# ESP32.net
KiCad netlist of a schematic drawn in Altium Designer
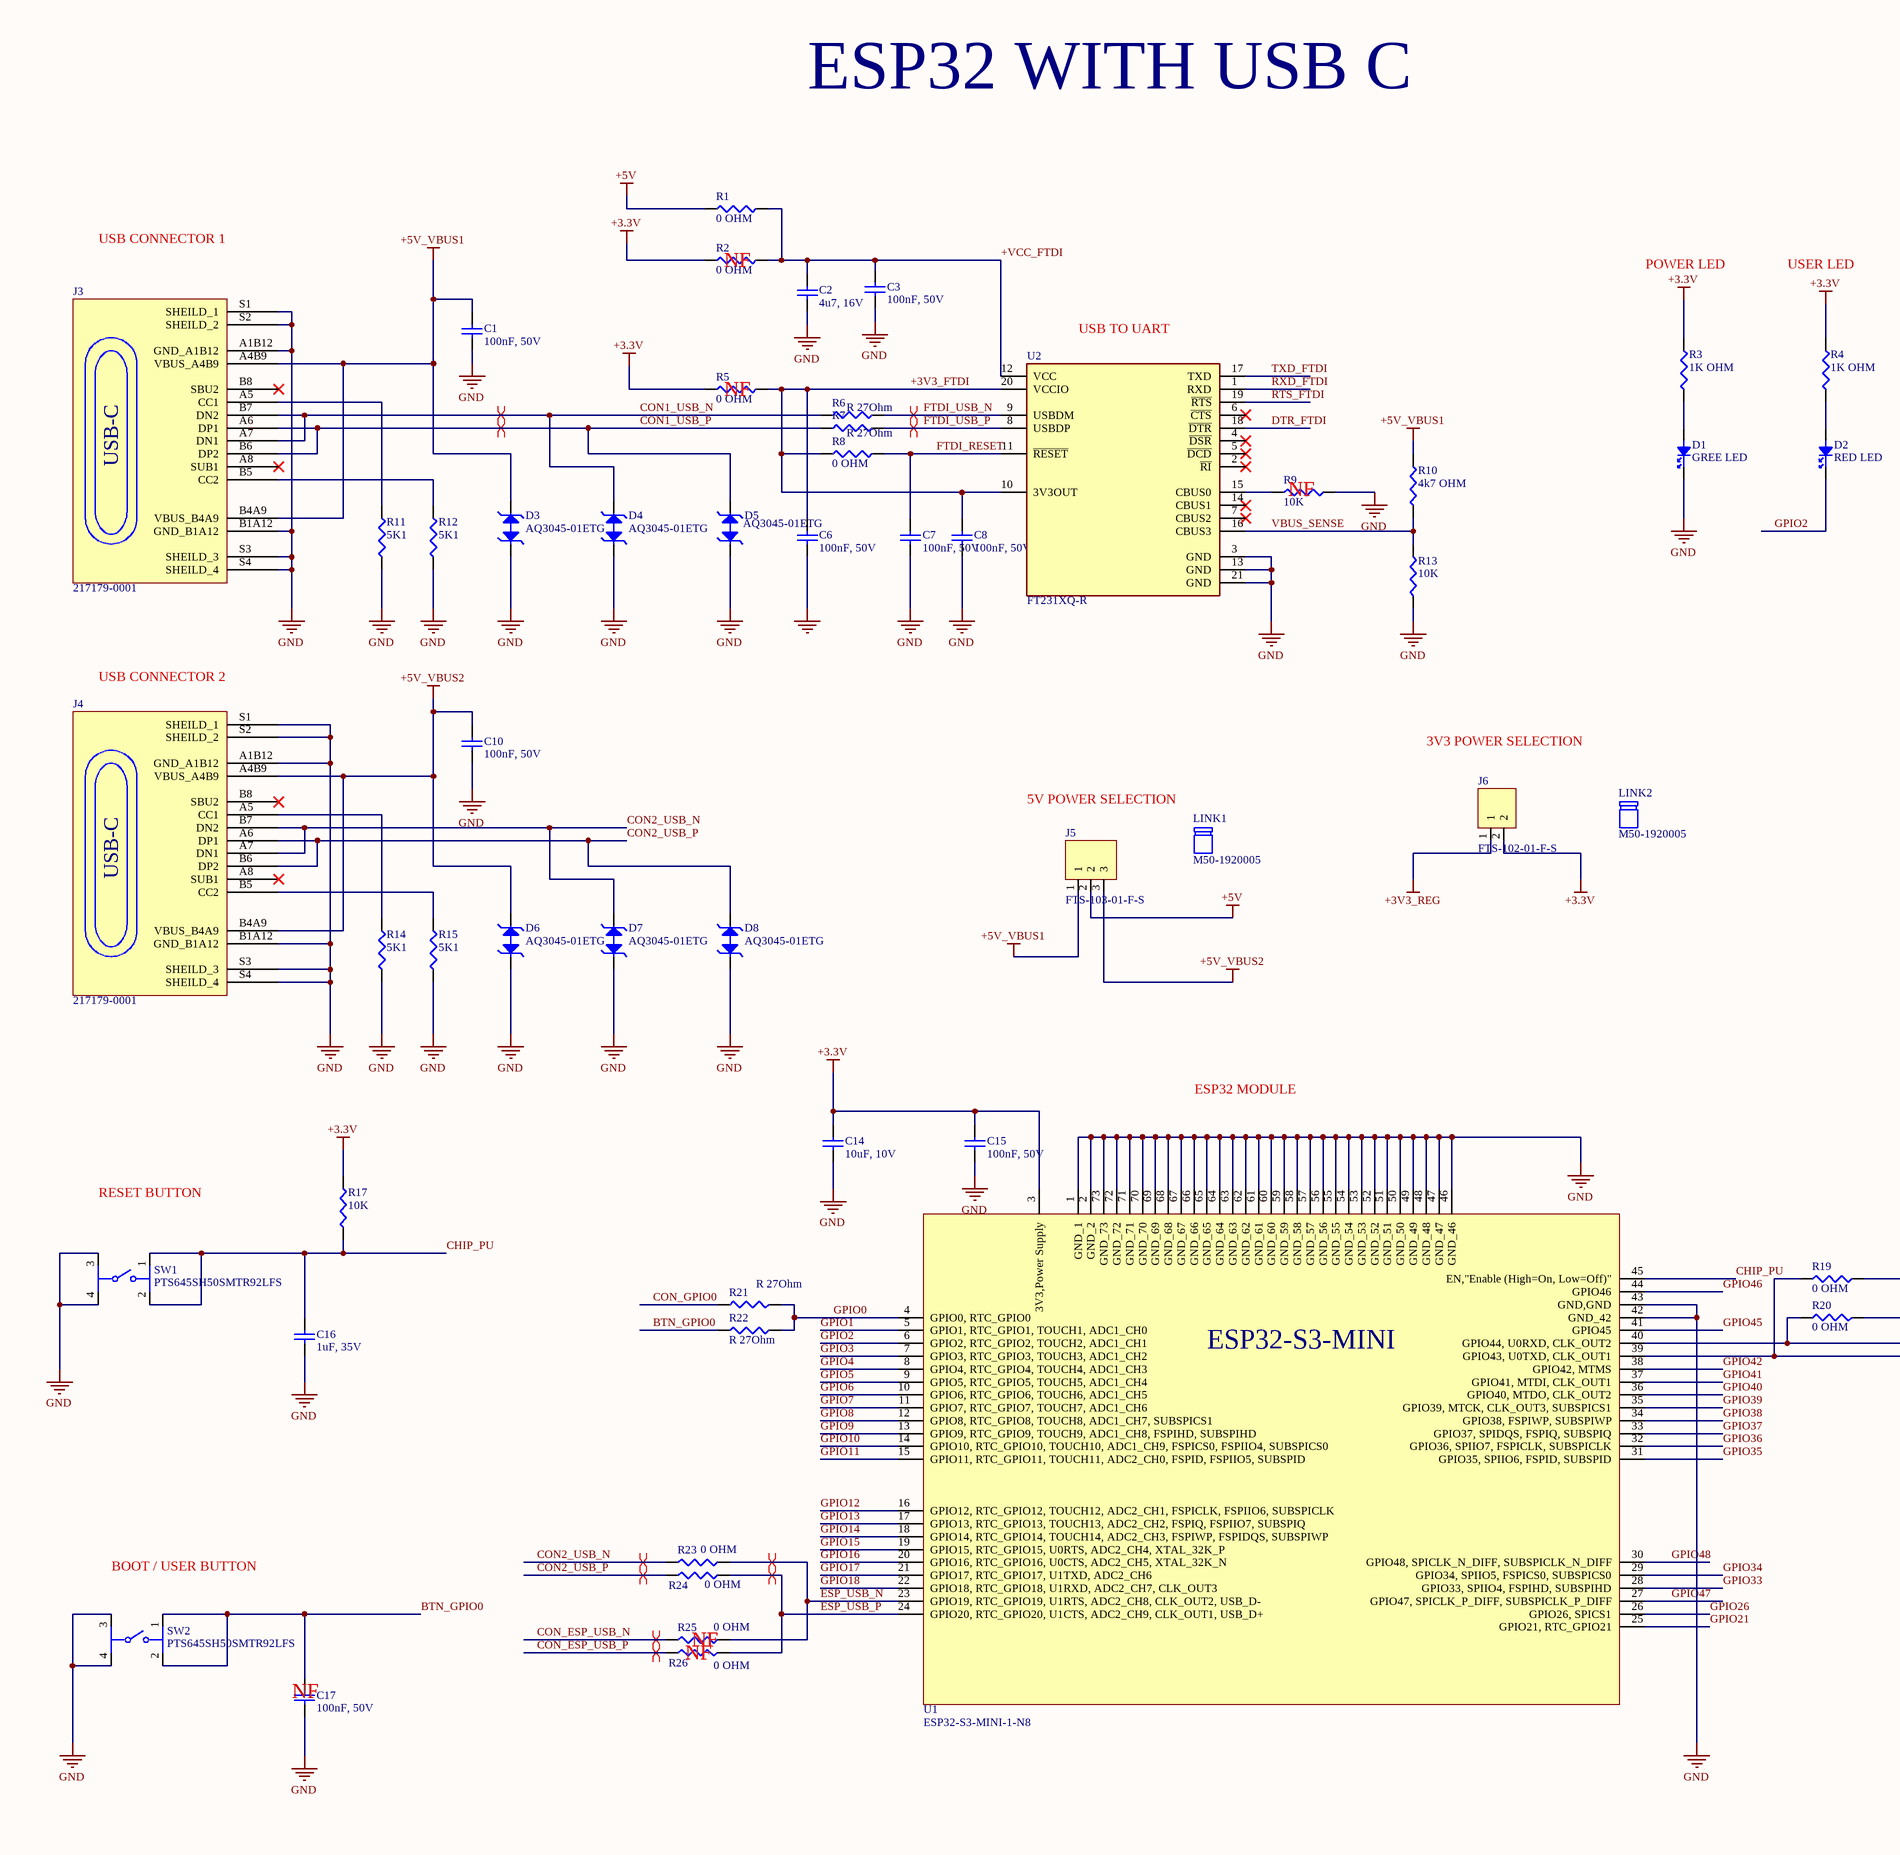
[diagram p0: ESP32.SchDoc, left]
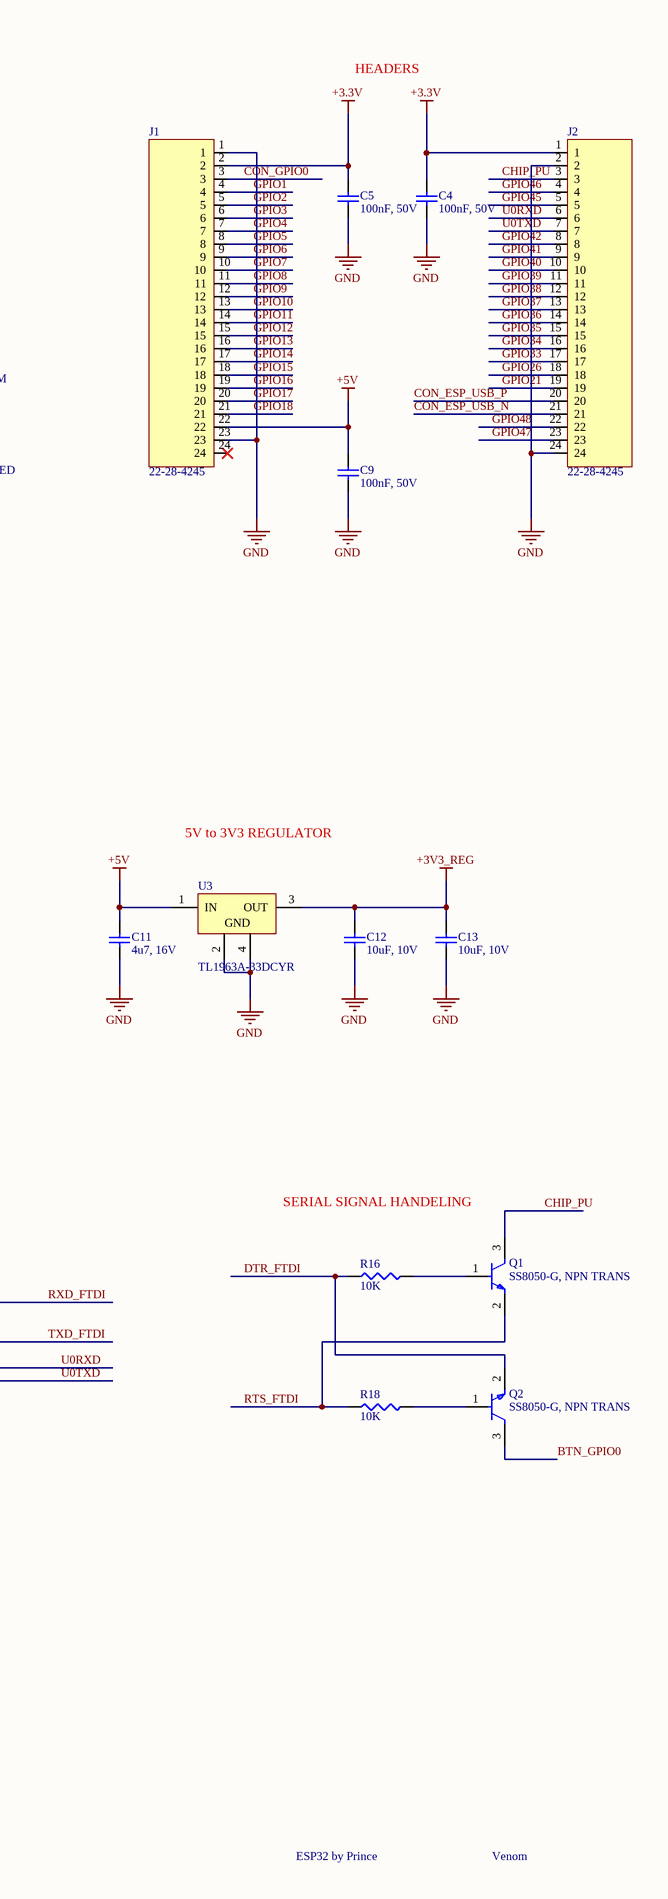
[diagram p1: ESP32.SchDoc, right]

(export (version "E")
  (design (tool "Eeschema 10.0.6"))
  (components
    (comp (ref "C1")
      (value "100nF, 50V")
      (footprint "CAPC1005X65N")
      (description "CAP CER 0.1UF 50V X7R 0402")
      (fields
        (field (name "MANUFACTURER") "Samsung Electro-Mechanics")
        (field (name "MANUFACTURER PART NUMBER") "CL05B104KB5NNNC")
      )
      (libsource (lib "Schlib") (part "CL05B104KB5NNNC"))
    )
    (comp (ref "C2")
      (value "4u7, 16V")
      (footprint "CAPC1005X65N")
      (description "CAP CER 4.7UF 16V X5R 0402")
      (fields
        (field (name "MANUFACTURER") "Samsung Electro-Mechanics")
        (field (name "MANUFACTURER PART NUMBER") "CL05A475MO5NUNC")
      )
      (libsource (lib "Schlib") (part "CL05A475MO5NUNC"))
    )
    (comp (ref "C3")
      (value "100nF, 50V")
      (footprint "CAPC1005X65N")
      (description "CAP CER 0.1UF 50V X7R 0402")
      (fields
        (field (name "MANUFACTURER") "Samsung Electro-Mechanics")
        (field (name "MANUFACTURER PART NUMBER") "CL05B104KB5NNNC")
      )
      (libsource (lib "Schlib") (part "CL05B104KB5NNNC"))
    )
    (comp (ref "C4")
      (value "100nF, 50V")
      (footprint "CAPC1005X65N")
      (description "CAP CER 0.1UF 50V X7R 0402")
      (fields
        (field (name "MANUFACTURER") "Samsung Electro-Mechanics")
        (field (name "MANUFACTURER PART NUMBER") "CL05B104KB5NNNC")
      )
      (libsource (lib "Schlib") (part "CL05B104KB5NNNC"))
    )
    (comp (ref "C5")
      (value "100nF, 50V")
      (footprint "CAPC1005X65N")
      (description "CAP CER 0.1UF 50V X7R 0402")
      (fields
        (field (name "MANUFACTURER") "Samsung Electro-Mechanics")
        (field (name "MANUFACTURER PART NUMBER") "CL05B104KB5NNNC")
      )
      (libsource (lib "Schlib") (part "CL05B104KB5NNNC"))
    )
    (comp (ref "C6")
      (value "100nF, 50V")
      (footprint "CAPC1005X65N")
      (description "CAP CER 0.1UF 50V X7R 0402")
      (fields
        (field (name "MANUFACTURER") "Samsung Electro-Mechanics")
        (field (name "MANUFACTURER PART NUMBER") "CL05B104KB5NNNC")
      )
      (libsource (lib "Schlib") (part "CL05B104KB5NNNC"))
    )
    (comp (ref "C7")
      (value "100nF, 50V")
      (footprint "CAPC1005X65N")
      (description "CAP CER 0.1UF 50V X7R 0402")
      (fields
        (field (name "MANUFACTURER") "Samsung Electro-Mechanics")
        (field (name "MANUFACTURER PART NUMBER") "CL05B104KB5NNNC")
      )
      (libsource (lib "Schlib") (part "CL05B104KB5NNNC"))
    )
    (comp (ref "C8")
      (value "100nF, 50V")
      (footprint "CAPC1005X65N")
      (description "CAP CER 0.1UF 50V X7R 0402")
      (fields
        (field (name "MANUFACTURER") "Samsung Electro-Mechanics")
        (field (name "MANUFACTURER PART NUMBER") "CL05B104KB5NNNC")
      )
      (libsource (lib "Schlib") (part "CL05B104KB5NNNC"))
    )
    (comp (ref "C9")
      (value "100nF, 50V")
      (footprint "CAPC1005X65N")
      (description "CAP CER 0.1UF 50V X7R 0402")
      (fields
        (field (name "MANUFACTURER") "Samsung Electro-Mechanics")
        (field (name "MANUFACTURER PART NUMBER") "CL05B104KB5NNNC")
      )
      (libsource (lib "Schlib") (part "CL05B104KB5NNNC"))
    )
    (comp (ref "C10")
      (value "100nF, 50V")
      (footprint "CAPC1005X65N")
      (description "CAP CER 0.1UF 50V X7R 0402")
      (fields
        (field (name "MANUFACTURER") "Samsung Electro-Mechanics")
        (field (name "MANUFACTURER PART NUMBER") "CL05B104KB5NNNC")
      )
      (libsource (lib "Schlib") (part "CL05B104KB5NNNC"))
    )
    (comp (ref "C11")
      (value "4u7, 16V")
      (footprint "CAPC1005X65N")
      (description "CAP CER 4.7UF 16V X5R 0402")
      (fields
        (field (name "MANUFACTURER") "Samsung Electro-Mechanics")
        (field (name "MANUFACTURER PART NUMBER") "CL05A475MO5NUNC")
      )
      (libsource (lib "Schlib") (part "CL05A475MO5NUNC"))
    )
    (comp (ref "C12")
      (value "10uF, 10V")
      (footprint "CAPC1005X65N")
      (description "CAP CER 10UF 10V X5R 0402")
      (fields
        (field (name "MANUFACTURER") "Samsung Electro-Mechanics")
        (field (name "MANUFACTURER PART NUMBER") "CL05A106MP8NUB8")
      )
      (libsource (lib "Schlib") (part "CL05A106MP8NUB8"))
    )
    (comp (ref "C13")
      (value "10uF, 10V")
      (footprint "CAPC1005X65N")
      (description "CAP CER 10UF 10V X5R 0402")
      (fields
        (field (name "MANUFACTURER") "Samsung Electro-Mechanics")
        (field (name "MANUFACTURER PART NUMBER") "CL05A106MP8NUB8")
      )
      (libsource (lib "Schlib") (part "CL05A106MP8NUB8"))
    )
    (comp (ref "C14")
      (value "10uF, 10V")
      (footprint "CAPC1005X65N")
      (description "CAP CER 10UF 10V X5R 0402")
      (fields
        (field (name "MANUFACTURER") "Samsung Electro-Mechanics")
        (field (name "MANUFACTURER PART NUMBER") "CL05A106MP8NUB8")
      )
      (libsource (lib "Schlib") (part "CL05A106MP8NUB8"))
    )
    (comp (ref "C15")
      (value "100nF, 50V")
      (footprint "CAPC1005X65N")
      (description "CAP CER 0.1UF 50V X7R 0402")
      (fields
        (field (name "MANUFACTURER") "Samsung Electro-Mechanics")
        (field (name "MANUFACTURER PART NUMBER") "CL05B104KB5NNNC")
      )
      (libsource (lib "Schlib") (part "CL05B104KB5NNNC"))
    )
    (comp (ref "C16")
      (value "1uF, 35V")
      (footprint "CAPC1005X65N")
      (description "CAP CER 1UF 35V X5R 0402")
      (fields
        (field (name "MANUFACTURER") "Samsung Electro-Mechanics")
        (field (name "MANUFACTURER PART NUMBER") "CL05A105KL5NRNC")
      )
      (libsource (lib "Schlib") (part "CL05A105KL5NRNC"))
    )
    (comp (ref "C17")
      (value "100nF, 50V")
      (footprint "CAPC1005X65N")
      (description "CAP CER 0.1UF 50V X7R 0402")
      (fields
        (field (name "MANUFACTURER") "Samsung Electro-Mechanics")
        (field (name "MANUFACTURER PART NUMBER") "CL05B104KB5NNNC")
      )
      (libsource (lib "Schlib") (part "CL05B104KB5NNNC"))
    )
    (comp (ref "D1")
      (value "GREE LED")
      (footprint "VLMG1500-GS08")
      (description "LED YLW-GRN 0402 SMD")
      (fields
        (field (name "MANUFACTURER") "Vishay")
        (field (name "MANUFACTURER PART NUMBER") "VLMG1500-GS08")
      )
      (libsource (lib "Schlib") (part "VLMG1500-GS08"))
    )
    (comp (ref "D2")
      (value "RED LED")
      (footprint "VLMS1500-GS08")
      (description "LED RED 0402 SMD")
      (fields
        (field (name "MANUFACTURER") "Vishay")
        (field (name "MANUFACTURER PART NUMBER") "VLMS1500-GS08")
      )
      (libsource (lib "Schlib") (part "VLMS1500-GS08"))
    )
    (comp (ref "D3")
      (value "AQ3045-01ETG")
      (footprint "SOD882")
      (description "TVS DIODE 5.3VWM 12VC SOD882")
      (fields (field (name "MANUFACTURER") "Littelfuse") (field (name "LCSC PART NUMBER") "C3710326"))
      (libsource (lib "Schlib") (part "AQ3045-01ETG"))
    )
    (comp (ref "D4")
      (value "AQ3045-01ETG")
      (footprint "SOD882")
      (description "TVS DIODE 5.3VWM 12VC SOD882")
      (fields (field (name "MANUFACTURER") "Littelfuse") (field (name "LCSC PART NUMBER") "C3710326"))
      (libsource (lib "Schlib") (part "AQ3045-01ETG"))
    )
    (comp (ref "D5")
      (value "AQ3045-01ETG")
      (footprint "SOD882")
      (description "TVS DIODE 5.3VWM 12VC SOD882")
      (fields (field (name "MANUFACTURER") "Littelfuse") (field (name "LCSC PART NUMBER") "C3710326"))
      (libsource (lib "Schlib") (part "AQ3045-01ETG"))
    )
    (comp (ref "D6")
      (value "AQ3045-01ETG")
      (footprint "SOD882")
      (description "TVS DIODE 5.3VWM 12VC SOD882")
      (fields (field (name "MANUFACTURER") "Littelfuse") (field (name "LCSC PART NUMBER") "C3710326"))
      (libsource (lib "Schlib") (part "AQ3045-01ETG"))
    )
    (comp (ref "D7")
      (value "AQ3045-01ETG")
      (footprint "SOD882")
      (description "TVS DIODE 5.3VWM 12VC SOD882")
      (fields (field (name "MANUFACTURER") "Littelfuse") (field (name "LCSC PART NUMBER") "C3710326"))
      (libsource (lib "Schlib") (part "AQ3045-01ETG"))
    )
    (comp (ref "D8")
      (value "AQ3045-01ETG")
      (footprint "SOD882")
      (description "TVS DIODE 5.3VWM 12VC SOD882")
      (fields (field (name "MANUFACTURER") "Littelfuse") (field (name "LCSC PART NUMBER") "C3710326"))
      (libsource (lib "Schlib") (part "AQ3045-01ETG"))
    )
    (comp (ref "J1")
      (value "22-28-4245")
      (footprint "HDR_1X24_2.54MM")
      (description "CONN HEADER VERT 24POS 2.54MM")
      (fields (field (name "MANUFACTURER") "Molex") (field (name "LCSC PART NUMBER") "C7145888"))
      (libsource (lib "Schlib") (part "22-28-4245"))
    )
    (comp (ref "J2")
      (value "22-28-4245")
      (footprint "HDR_1X24_2.54MM")
      (description "CONN HEADER VERT 24POS 2.54MM")
      (fields (field (name "MANUFACTURER") "Molex") (field (name "LCSC PART NUMBER") "C7145888"))
      (libsource (lib "") (part "22-28-4245_1"))
    )
    (comp (ref "J3")
      (value "217179-0001")
      (footprint "FP-2171790001-MFG")
      (description "CONN RCP USB2.0 TYP C 24P SMD RA")
      (fields (field (name "MANUFACTURER") "Molex") (field (name "LCSC PART NUMBER") "C3197684"))
      (libsource (lib "Schlib") (part "217179-0001"))
    )
    (comp (ref "J4")
      (value "217179-0001")
      (footprint "FP-2171790001-MFG")
      (description "CONN RCP USB2.0 TYP C 24P SMD RA")
      (fields (field (name "MANUFACTURER") "Molex") (field (name "LCSC PART NUMBER") "C3197684"))
      (libsource (lib "Schlib") (part "217179-0001"))
    )
    (comp (ref "J5")
      (value "FTS-103-01-F-S")
      (footprint "HDR_1X3_1.27MM")
      (description "CONN HEADER VERT 3POS 1.27MM")
      (fields (field (name "MANUFACTURER") "Samtec") (field (name "LCSC PART NUMBER") "C3333578"))
      (libsource (lib "Schlib") (part "FTS-103-01-F-S"))
    )
    (comp (ref "J6")
      (value "FTS-102-01-F-S")
      (footprint "HDR_1X2_1.27MM")
      (description "CONN HEADER VERT 2POS 1.27MM")
      (fields (field (name "MANUFACTURER") "Samtec") (field (name "LCSC PART NUMBER") "C6045317"))
      (libsource (lib "Schlib") (part "FTS-102-01-F-S"))
    )
    (comp (ref "LINK1")
      (value "M50-1920005")
      (description "CONN SHUNT 1.27MM RED")
      (fields (field (name "MANUFACTURER") "Harwin") (field (name "LCSC PART NUMBER") "C6985646"))
      (libsource (lib "Schlib") (part "M50-1920005"))
    )
    (comp (ref "LINK2")
      (value "M50-1920005")
      (description "CONN SHUNT 1.27MM RED")
      (fields (field (name "MANUFACTURER") "Harwin") (field (name "LCSC PART NUMBER") "C6985646"))
      (libsource (lib "Schlib") (part "M50-1920005"))
    )
    (comp (ref "Q1")
      (value "SS8050-G, NPN TRANS")
      (footprint "FP-SS8050-G-IPC_B")
      (description "TRANS NPN 25V 1.5A SOT-23-3")
      (fields (field (name "MANUFACTURER") "Comchip") (field (name "MANUFACTURER PART NUMBER") "SS8050-G"))
      (libsource (lib "Schlib") (part "SS8050-G"))
    )
    (comp (ref "Q2")
      (value "SS8050-G, NPN TRANS")
      (footprint "FP-SS8050-G-IPC_B")
      (description "TRANS NPN 25V 1.5A SOT-23-3")
      (fields (field (name "MANUFACTURER") "Comchip") (field (name "MANUFACTURER PART NUMBER") "SS8050-G"))
      (libsource (lib "Schlib") (part "SS8050-G"))
    )
    (comp (ref "R1")
      (value "0 OHM")
      (footprint "RESC1005X40")
      (description "RES 0 OHM JUMPER 1/16W 0402")
      (fields
        (field (name "MANUFACTURER") "Yageo Group")
        (field (name "MANUFACTURER PART NUMBER") "RC0402JR-070RL")
      )
      (libsource (lib "Schlib") (part "RC0402JR-070RL"))
    )
    (comp (ref "R2")
      (value "0 OHM")
      (footprint "RESC1005X40")
      (description "RES 0 OHM JUMPER 1/16W 0402")
      (fields
        (field (name "MANUFACTURER") "Yageo Group")
        (field (name "MANUFACTURER PART NUMBER") "RC0402JR-070RL")
      )
      (libsource (lib "Schlib") (part "RC0402JR-070RL"))
    )
    (comp (ref "R3")
      (value "1K OHM")
      (footprint "RESC1005X40")
      (description "RES 1K OHM 1% 1/16W 0402")
      (fields
        (field (name "MANUFACTURER") "Yageo Group")
        (field (name "MANUFACTURER PART NUMBER") "RC0402FR-071KL")
      )
      (libsource (lib "Schlib") (part "RC0402FR-071KL"))
    )
    (comp (ref "R4")
      (value "1K OHM")
      (footprint "RESC1005X40")
      (description "RES 1K OHM 1% 1/16W 0402")
      (fields
        (field (name "MANUFACTURER") "Yageo Group")
        (field (name "MANUFACTURER PART NUMBER") "RC0402FR-071KL")
      )
      (libsource (lib "Schlib") (part "RC0402FR-071KL"))
    )
    (comp (ref "R5")
      (value "0 OHM")
      (footprint "RESC1005X40")
      (description "RES 0 OHM JUMPER 1/16W 0402")
      (fields
        (field (name "MANUFACTURER") "Yageo Group")
        (field (name "MANUFACTURER PART NUMBER") "RC0402JR-070RL")
      )
      (libsource (lib "Schlib") (part "RC0402JR-070RL"))
    )
    (comp (ref "R6")
      (value "R 27Ohm")
      (footprint "RESC1005X40")
      (description "RES 27 OHM 1% 1/16W 0402")
      (fields
        (field (name "MANUFACTURER") "Yageo Group")
        (field (name "MANUFACTURER PART NUMBER") "RC0402FR-0727RL")
      )
      (libsource (lib "Schlib") (part "RC0402FR-0727RL"))
    )
    (comp (ref "R7")
      (value "R 27Ohm")
      (footprint "RESC1005X40")
      (description "RES 27 OHM 1% 1/16W 0402")
      (fields
        (field (name "MANUFACTURER") "Yageo Group")
        (field (name "MANUFACTURER PART NUMBER") "RC0402FR-0727RL")
      )
      (libsource (lib "Schlib") (part "RC0402FR-0727RL"))
    )
    (comp (ref "R8")
      (value "0 OHM")
      (footprint "RESC1005X40")
      (description "RES 0 OHM JUMPER 1/16W 0402")
      (fields
        (field (name "MANUFACTURER") "Yageo Group")
        (field (name "MANUFACTURER PART NUMBER") "RC0402JR-070RL")
      )
      (libsource (lib "Schlib") (part "RC0402JR-070RL"))
    )
    (comp (ref "R9")
      (value "10K")
      (footprint "RESC1005X40")
      (description "RES SMD 10K OHM 1% 1/16W 0402")
      (fields
        (field (name "MANUFACTURER") "Yageo Group")
        (field (name "MANUFACTURER PART NUMBER") "AC0402FR-0710KL")
      )
      (libsource (lib "Schlib") (part "AC0402FR-0710KL"))
    )
    (comp (ref "R10")
      (value "4k7 OHM")
      (footprint "RESC1005X40")
      (description "RES 4.7K OHM 1% 1/16W 0402")
      (fields
        (field (name "MANUFACTURER") "Yageo Group")
        (field (name "MANUFACTURER PART NUMBER") "RC0402FR-074K7L")
      )
      (libsource (lib "Schlib") (part "RC0402FR-074K7L"))
    )
    (comp (ref "R11")
      (value "5K1")
      (footprint "RESC1005X40")
      (description "RES SMD 5.1K OHM 1% 1/16W 0402")
      (fields
        (field (name "MANUFACTURER") "Yageo Group")
        (field (name "MANUFACTURER PART NUMBER") "AC0402FR-075K1L")
      )
      (libsource (lib "Schlib") (part "AC0402FR-075K1L"))
    )
    (comp (ref "R12")
      (value "5K1")
      (footprint "RESC1005X40")
      (description "RES SMD 5.1K OHM 1% 1/16W 0402")
      (fields
        (field (name "MANUFACTURER") "Yageo Group")
        (field (name "MANUFACTURER PART NUMBER") "AC0402FR-075K1L")
      )
      (libsource (lib "Schlib") (part "AC0402FR-075K1L"))
    )
    (comp (ref "R13")
      (value "10K")
      (footprint "RESC1005X40")
      (description "RES SMD 10K OHM 1% 1/16W 0402")
      (fields
        (field (name "MANUFACTURER") "Yageo Group")
        (field (name "MANUFACTURER PART NUMBER") "AC0402FR-0710KL")
      )
      (libsource (lib "Schlib") (part "AC0402FR-0710KL"))
    )
    (comp (ref "R14")
      (value "5K1")
      (footprint "RESC1005X40")
      (description "RES SMD 5.1K OHM 1% 1/16W 0402")
      (fields
        (field (name "MANUFACTURER") "Yageo Group")
        (field (name "MANUFACTURER PART NUMBER") "AC0402FR-075K1L")
      )
      (libsource (lib "Schlib") (part "AC0402FR-075K1L"))
    )
    (comp (ref "R15")
      (value "5K1")
      (footprint "RESC1005X40")
      (description "RES SMD 5.1K OHM 1% 1/16W 0402")
      (fields
        (field (name "MANUFACTURER") "Yageo Group")
        (field (name "MANUFACTURER PART NUMBER") "AC0402FR-075K1L")
      )
      (libsource (lib "Schlib") (part "AC0402FR-075K1L"))
    )
    (comp (ref "R16")
      (value "10K")
      (footprint "RESC1005X40")
      (description "RES SMD 10K OHM 1% 1/16W 0402")
      (fields
        (field (name "MANUFACTURER") "Yageo Group")
        (field (name "MANUFACTURER PART NUMBER") "AC0402FR-0710KL")
      )
      (libsource (lib "Schlib") (part "AC0402FR-0710KL"))
    )
    (comp (ref "R17")
      (value "10K")
      (footprint "RESC1005X40")
      (description "RES SMD 10K OHM 1% 1/16W 0402")
      (fields
        (field (name "MANUFACTURER") "Yageo Group")
        (field (name "MANUFACTURER PART NUMBER") "AC0402FR-0710KL")
      )
      (libsource (lib "Schlib") (part "AC0402FR-0710KL"))
    )
    (comp (ref "R18")
      (value "10K")
      (footprint "RESC1005X40")
      (description "RES SMD 10K OHM 1% 1/16W 0402")
      (fields
        (field (name "MANUFACTURER") "Yageo Group")
        (field (name "MANUFACTURER PART NUMBER") "AC0402FR-0710KL")
      )
      (libsource (lib "Schlib") (part "AC0402FR-0710KL"))
    )
    (comp (ref "R19")
      (value "0 OHM")
      (footprint "RESC1005X40")
      (description "RES 0 OHM JUMPER 1/16W 0402")
      (fields
        (field (name "MANUFACTURER") "Yageo Group")
        (field (name "MANUFACTURER PART NUMBER") "RC0402JR-070RL")
      )
      (libsource (lib "Schlib") (part "RC0402JR-070RL"))
    )
    (comp (ref "R20")
      (value "0 OHM")
      (footprint "RESC1005X40")
      (description "RES 0 OHM JUMPER 1/16W 0402")
      (fields
        (field (name "MANUFACTURER") "Yageo Group")
        (field (name "MANUFACTURER PART NUMBER") "RC0402JR-070RL")
      )
      (libsource (lib "Schlib") (part "RC0402JR-070RL"))
    )
    (comp (ref "R21")
      (value "R 27Ohm")
      (footprint "RESC1005X40")
      (description "RES 27 OHM 1% 1/16W 0402")
      (fields
        (field (name "MANUFACTURER") "Yageo Group")
        (field (name "MANUFACTURER PART NUMBER") "RC0402FR-0727RL")
      )
      (libsource (lib "Schlib") (part "RC0402FR-0727RL"))
    )
    (comp (ref "R22")
      (value "R 27Ohm")
      (footprint "RESC1005X40")
      (description "RES 27 OHM 1% 1/16W 0402")
      (fields
        (field (name "MANUFACTURER") "Yageo Group")
        (field (name "MANUFACTURER PART NUMBER") "RC0402FR-0727RL")
      )
      (libsource (lib "Schlib") (part "RC0402FR-0727RL"))
    )
    (comp (ref "R23")
      (value "0 OHM")
      (footprint "RESC1005X40")
      (description "RES 0 OHM JUMPER 1/16W 0402")
      (fields
        (field (name "MANUFACTURER") "Yageo Group")
        (field (name "MANUFACTURER PART NUMBER") "RC0402JR-070RL")
      )
      (libsource (lib "Schlib") (part "RC0402JR-070RL"))
    )
    (comp (ref "R24")
      (value "0 OHM")
      (footprint "RESC1005X40")
      (description "RES 0 OHM JUMPER 1/16W 0402")
      (fields
        (field (name "MANUFACTURER") "Yageo Group")
        (field (name "MANUFACTURER PART NUMBER") "RC0402JR-070RL")
      )
      (libsource (lib "Schlib") (part "RC0402JR-070RL"))
    )
    (comp (ref "R25")
      (value "0 OHM")
      (footprint "RESC1005X40")
      (description "RES 0 OHM JUMPER 1/16W 0402")
      (fields
        (field (name "MANUFACTURER") "Yageo Group")
        (field (name "MANUFACTURER PART NUMBER") "RC0402JR-070RL")
      )
      (libsource (lib "Schlib") (part "RC0402JR-070RL"))
    )
    (comp (ref "R26")
      (value "0 OHM")
      (footprint "RESC1005X40")
      (description "RES 0 OHM JUMPER 1/16W 0402")
      (fields
        (field (name "MANUFACTURER") "Yageo Group")
        (field (name "MANUFACTURER PART NUMBER") "RC0402JR-070RL")
      )
      (libsource (lib "Schlib") (part "RC0402JR-070RL"))
    )
    (comp (ref "SW1")
      (value "PTS645SH50SMTR92LFS")
      (footprint "FP-PTS645SH50SMTR92LFS-MFG")
      (description "SWITCH TACTILE SPST-NO 0.05A 12V")
      (fields (field (name "MANUFACTURER") "C&K Components") (field (name "LCSC PART NUMBER") "C285463"))
      (libsource (lib "Schlib") (part "PTS645SH50SMTR92LFS"))
    )
    (comp (ref "SW2")
      (value "PTS645SH50SMTR92LFS")
      (footprint "FP-PTS645SH50SMTR92LFS-MFG")
      (description "SWITCH TACTILE SPST-NO 0.05A 12V")
      (fields (field (name "MANUFACTURER") "C&K Components") (field (name "LCSC PART NUMBER") "C285463"))
      (libsource (lib "Schlib") (part "PTS645SH50SMTR92LFS"))
    )
    (comp (ref "U1")
      (value "ESP32-S3-MINI-1-N8")
      (footprint "XCVR_ESP32-S3-MINI-1-N8")
      (description "SMD module, ESP32-S3FN8, 8 MB SPI flash, PCB antenna")
      (fields (field (name "MANUFACTURER") "Espressif Systems") (field (name "LCSC PART NUMBER") "C2913206"))
      (libsource (lib "Schlib") (part "ESP32-S3-MINI-1-N8"))
    )
    (comp (ref "U2")
      (value "FT231XQ-R")
      (footprint "FP-QFN-20-IPC_B")
      (description "IC USB SERIAL FULL UART 20QFN")
      (fields (field (name "MANUFACTURER") "FTDI") (field (name "LCSC PART NUMBER") "C132159"))
      (libsource (lib "Schlib") (part "FT231XQ-R"))
    )
    (comp (ref "U3")
      (value "TL1963A-33DCYR")
      (footprint "DCY0004A_N")
      (description "IC REG LIN 3.3V 1.5A SOT-223-4")
      (fields (field (name "MANUFACTURER") "Texas Instruments") (field (name "LCSC PART NUMBER") "C181262"))
      (libsource (lib "Schlib") (part "TL1963A-33DCYR"))
    )
  )
  (nets
    (net (code "1") (name "+3.3V") (class "Default")
      (node (ref "C14") (pin "2") (pinfunction "2_2") (pintype "passive"))
      (node (ref "C15") (pin "2") (pinfunction "2_2") (pintype "passive"))
      (node (ref "C4") (pin "2") (pinfunction "2_2") (pintype "passive"))
      (node (ref "C5") (pin "2") (pinfunction "2_2") (pintype "passive"))
      (node (ref "J1") (pin "2") (pinfunction "2_2") (pintype "passive"))
      (node (ref "J2") (pin "1") (pinfunction "1_1") (pintype "passive"))
      (node (ref "J6") (pin "2") (pinfunction "2_2") (pintype "passive"))
      (node (ref "R17") (pin "2") (pinfunction "2_2") (pintype "passive"))
      (node (ref "R2") (pin "1") (pinfunction "1_1") (pintype "passive"))
      (node (ref "R3") (pin "2") (pinfunction "2_2") (pintype "passive"))
      (node (ref "R4") (pin "2") (pinfunction "2_2") (pintype "passive"))
      (node (ref "R5") (pin "1") (pinfunction "1_1") (pintype "passive"))
      (node (ref "U1") (pin "3") (pinfunction "3V3,Power_Supply_3") (pintype "passive"))
    )
    (net (code "2") (name "+3V3_REG") (class "Default")
      (node (ref "C12") (pin "2") (pinfunction "2_2") (pintype "passive"))
      (node (ref "C13") (pin "2") (pinfunction "2_2") (pintype "passive"))
      (node (ref "J6") (pin "1") (pinfunction "1_1") (pintype "passive"))
      (node (ref "U3") (pin "3") (pinfunction "OUT_3") (pintype "power_in"))
    )
    (net (code "3") (name "+5V") (class "Default")
      (node (ref "C11") (pin "2") (pinfunction "2_2") (pintype "passive"))
      (node (ref "C9") (pin "2") (pinfunction "2_2") (pintype "passive"))
      (node (ref "J1") (pin "22") (pinfunction "22_22") (pintype "passive"))
      (node (ref "J5") (pin "2") (pinfunction "2_2") (pintype "passive"))
      (node (ref "R1") (pin "1") (pinfunction "1_1") (pintype "passive"))
      (node (ref "U3") (pin "1") (pinfunction "IN_1") (pintype "power_in"))
    )
    (net (code "4") (name "+5V_VBUS1") (class "Default")
      (node (ref "C1") (pin "2") (pinfunction "2_2") (pintype "passive"))
      (node (ref "D3") (pin "2") (pinfunction "2_2") (pintype "passive"))
      (node (ref "J3") (pin "A4B9") (pinfunction "VBUS_A4B9_A4B9") (pintype "passive"))
      (node (ref "J3") (pin "B4A9") (pinfunction "VBUS_B4A9_B4A9") (pintype "passive"))
      (node (ref "J5") (pin "1") (pinfunction "1_1") (pintype "passive"))
      (node (ref "R10") (pin "2") (pinfunction "2_2") (pintype "passive"))
    )
    (net (code "5") (name "+5V_VBUS2") (class "Default")
      (node (ref "C10") (pin "2") (pinfunction "2_2") (pintype "passive"))
      (node (ref "D6") (pin "2") (pinfunction "2_2") (pintype "passive"))
      (node (ref "J4") (pin "A4B9") (pinfunction "VBUS_A4B9_A4B9") (pintype "passive"))
      (node (ref "J4") (pin "B4A9") (pinfunction "VBUS_B4A9_B4A9") (pintype "passive"))
      (node (ref "J5") (pin "3") (pinfunction "3_3") (pintype "passive"))
    )
    (net (code "6") (name "/+3V3_FTDI") (class "Default")
      (node (ref "C6") (pin "1") (pinfunction "1_1") (pintype "passive"))
      (node (ref "C8") (pin "1") (pinfunction "1_1") (pintype "passive"))
      (node (ref "R5") (pin "2") (pinfunction "2_2") (pintype "passive"))
      (node (ref "R8") (pin "1") (pinfunction "1_1") (pintype "passive"))
      (node (ref "U2") (pin "10") (pinfunction "3V3OUT_10") (pintype "passive"))
      (node (ref "U2") (pin "20") (pinfunction "VCCIO_20") (pintype "passive"))
    )
    (net (code "7") (name "/+VCC_FTDI") (class "Default")
      (node (ref "C2") (pin "2") (pinfunction "2_2") (pintype "passive"))
      (node (ref "C3") (pin "1") (pinfunction "1_1") (pintype "passive"))
      (node (ref "R1") (pin "2") (pinfunction "2_2") (pintype "passive"))
      (node (ref "R2") (pin "2") (pinfunction "2_2") (pintype "passive"))
      (node (ref "U2") (pin "12") (pinfunction "VCC_12") (pintype "passive"))
    )
    (net (code "8") (name "/BTN_GPIO0") (class "Default")
      (node (ref "C17") (pin "2") (pinfunction "2_2") (pintype "passive"))
      (node (ref "Q2") (pin "3") (pinfunction "C_3") (pintype "passive"))
      (node (ref "R22") (pin "1") (pinfunction "1_1") (pintype "passive"))
      (node (ref "SW2") (pin "1") (pinfunction "1_1") (pintype "passive"))
      (node (ref "SW2") (pin "2") (pinfunction "2_2") (pintype "passive"))
    )
    (net (code "9") (name "/CHIP_PU") (class "Default")
      (node (ref "C16") (pin "2") (pinfunction "2_2") (pintype "passive"))
      (node (ref "J2") (pin "3") (pinfunction "3_3") (pintype "passive"))
      (node (ref "Q1") (pin "3") (pinfunction "C_3") (pintype "passive"))
      (node (ref "R17") (pin "1") (pinfunction "1_1") (pintype "passive"))
      (node (ref "SW1") (pin "1") (pinfunction "1_1") (pintype "passive"))
      (node (ref "SW1") (pin "2") (pinfunction "2_2") (pintype "passive"))
      (node (ref "U1") (pin "45") (pinfunction "EN,\"Enable_(High=On,_Low=Off)\"_45") (pintype "passive"))
    )
    (net (code "10") (name "/CON1_USB_N") (class "Default")
      (node (ref "D4") (pin "2") (pinfunction "2_2") (pintype "passive"))
      (node (ref "J3") (pin "A7") (pinfunction "DN1_A7") (pintype "passive"))
      (node (ref "J3") (pin "B7") (pinfunction "DN2_B7") (pintype "passive"))
      (node (ref "R6") (pin "1") (pinfunction "1_1") (pintype "passive"))
    )
    (net (code "11") (name "/CON1_USB_P") (class "Default")
      (node (ref "D5") (pin "2") (pinfunction "2_2") (pintype "passive"))
      (node (ref "J3") (pin "A6") (pinfunction "DP1_A6") (pintype "passive"))
      (node (ref "J3") (pin "B6") (pinfunction "DP2_B6") (pintype "passive"))
      (node (ref "R7") (pin "1") (pinfunction "1_1") (pintype "passive"))
    )
    (net (code "12") (name "/CON2_USB_N") (class "Default")
      (node (ref "D7") (pin "2") (pinfunction "2_2") (pintype "passive"))
      (node (ref "J4") (pin "A7") (pinfunction "DN1_A7") (pintype "passive"))
      (node (ref "J4") (pin "B7") (pinfunction "DN2_B7") (pintype "passive"))
      (node (ref "R23") (pin "1") (pinfunction "1_1") (pintype "passive"))
    )
    (net (code "13") (name "/CON2_USB_P") (class "Default")
      (node (ref "D8") (pin "2") (pinfunction "2_2") (pintype "passive"))
      (node (ref "J4") (pin "A6") (pinfunction "DP1_A6") (pintype "passive"))
      (node (ref "J4") (pin "B6") (pinfunction "DP2_B6") (pintype "passive"))
      (node (ref "R24") (pin "1") (pinfunction "1_1") (pintype "passive"))
    )
    (net (code "14") (name "/CON_ESP_USB_N") (class "Default")
      (node (ref "J2") (pin "21") (pinfunction "21_21") (pintype "passive"))
      (node (ref "R25") (pin "1") (pinfunction "1_1") (pintype "passive"))
    )
    (net (code "15") (name "/CON_ESP_USB_P") (class "Default")
      (node (ref "J2") (pin "20") (pinfunction "20_20") (pintype "passive"))
      (node (ref "R26") (pin "1") (pinfunction "1_1") (pintype "passive"))
    )
    (net (code "16") (name "/CON_GPIO0") (class "Default")
      (node (ref "J1") (pin "3") (pinfunction "3_3") (pintype "passive"))
      (node (ref "R21") (pin "1") (pinfunction "1_1") (pintype "passive"))
    )
    (net (code "17") (name "/DTR_FTDI") (class "Default")
      (node (ref "Q2") (pin "2") (pinfunction "E_2") (pintype "passive"))
      (node (ref "R16") (pin "1") (pinfunction "1_1") (pintype "passive"))
      (node (ref "U2") (pin "18") (pinfunction "~{DTR}_18") (pintype "passive"))
    )
    (net (code "18") (name "/ESP_USB_N") (class "Default")
      (node (ref "R23") (pin "2") (pinfunction "2_2") (pintype "passive"))
      (node (ref "R25") (pin "2") (pinfunction "2_2") (pintype "passive"))
      (node (ref "U1") (pin "23") (pinfunction "GPIO19,_RTC_GPIO19,_U1RTS,_ADC2_CH8,_CLK_OUT2,_USB_D-_23") (pintype "passive"))
    )
    (net (code "19") (name "/ESP_USB_P") (class "Default")
      (node (ref "R24") (pin "2") (pinfunction "2_2") (pintype "passive"))
      (node (ref "R26") (pin "2") (pinfunction "2_2") (pintype "passive"))
      (node (ref "U1") (pin "24") (pinfunction "GPIO20,_RTC_GPIO20,_U1CTS,_ADC2_CH9,_CLK_OUT1,_USB_D+_24") (pintype "passive"))
    )
    (net (code "20") (name "/FTDI_RESET") (class "Default")
      (node (ref "C7") (pin "1") (pinfunction "1_1") (pintype "passive"))
      (node (ref "R8") (pin "2") (pinfunction "2_2") (pintype "passive"))
      (node (ref "U2") (pin "11") (pinfunction "~{RESET}_11") (pintype "passive"))
    )
    (net (code "21") (name "/FTDI_USB_N") (class "Default")
      (node (ref "R6") (pin "2") (pinfunction "2_2") (pintype "passive"))
      (node (ref "U2") (pin "9") (pinfunction "USBDM_9") (pintype "passive"))
    )
    (net (code "22") (name "/FTDI_USB_P") (class "Default")
      (node (ref "R7") (pin "2") (pinfunction "2_2") (pintype "passive"))
      (node (ref "U2") (pin "8") (pinfunction "USBDP_8") (pintype "passive"))
    )
    (net (code "23") (name "/GPIO0") (class "Default")
      (node (ref "R21") (pin "2") (pinfunction "2_2") (pintype "passive"))
      (node (ref "R22") (pin "2") (pinfunction "2_2") (pintype "passive"))
      (node (ref "U1") (pin "4") (pinfunction "GPIO0,_RTC_GPIO0_4") (pintype "passive"))
    )
    (net (code "24") (name "/GPIO1") (class "Default")
      (node (ref "J1") (pin "4") (pinfunction "4_4") (pintype "passive"))
      (node (ref "U1") (pin "5") (pinfunction "GPIO1,_RTC_GPIO1,_TOUCH1,_ADC1_CH0_5") (pintype "passive"))
    )
    (net (code "25") (name "/GPIO2") (class "Default")
      (node (ref "D2") (pin "1") (pinfunction "1_1") (pintype "passive"))
      (node (ref "J1") (pin "5") (pinfunction "5_5") (pintype "passive"))
      (node (ref "U1") (pin "6") (pinfunction "GPIO2,_RTC_GPIO2,_TOUCH2,_ADC1_CH1_6") (pintype "passive"))
    )
    (net (code "26") (name "/GPIO3") (class "Default")
      (node (ref "J1") (pin "6") (pinfunction "6_6") (pintype "passive"))
      (node (ref "U1") (pin "7") (pinfunction "GPIO3,_RTC_GPIO3,_TOUCH3,_ADC1_CH2_7") (pintype "passive"))
    )
    (net (code "27") (name "/GPIO4") (class "Default")
      (node (ref "J1") (pin "7") (pinfunction "7_7") (pintype "passive"))
      (node (ref "U1") (pin "8") (pinfunction "GPIO4,_RTC_GPIO4,_TOUCH4,_ADC1_CH3_8") (pintype "passive"))
    )
    (net (code "28") (name "/GPIO5") (class "Default")
      (node (ref "J1") (pin "8") (pinfunction "8_8") (pintype "passive"))
      (node (ref "U1") (pin "9") (pinfunction "GPIO5,_RTC_GPIO5,_TOUCH5,_ADC1_CH4_9") (pintype "passive"))
    )
    (net (code "29") (name "/GPIO6") (class "Default")
      (node (ref "J1") (pin "9") (pinfunction "9_9") (pintype "passive"))
      (node (ref "U1") (pin "10") (pinfunction "GPIO6,_RTC_GPIO6,_TOUCH6,_ADC1_CH5_10") (pintype "passive"))
    )
    (net (code "30") (name "/GPIO7") (class "Default")
      (node (ref "J1") (pin "10") (pinfunction "10_10") (pintype "passive"))
      (node (ref "U1") (pin "11") (pinfunction "GPIO7,_RTC_GPIO7,_TOUCH7,_ADC1_CH6_11") (pintype "passive"))
    )
    (net (code "31") (name "/GPIO8") (class "Default")
      (node (ref "J1") (pin "11") (pinfunction "11_11") (pintype "passive"))
      (node (ref "U1") (pin "12") (pinfunction "GPIO8,_RTC_GPIO8,_TOUCH8,_ADC1_CH7,_SUBSPICS1_12") (pintype "passive"))
    )
    (net (code "32") (name "/GPIO9") (class "Default")
      (node (ref "J1") (pin "12") (pinfunction "12_12") (pintype "passive"))
      (node (ref "U1") (pin "13") (pinfunction "GPIO9,_RTC_GPIO9,_TOUCH9,_ADC1_CH8,_FSPIHD,_SUBSPIHD_13") (pintype "passive"))
    )
    (net (code "33") (name "/GPIO10") (class "Default")
      (node (ref "J1") (pin "13") (pinfunction "13_13") (pintype "passive"))
      (node (ref "U1") (pin "14") (pinfunction "GPIO10,_RTC_GPIO10,_TOUCH10,_ADC1_CH9,_FSPICS0,_FSPIIO4,_SUBSPICS0_14") (pintype "passive"))
    )
    (net (code "34") (name "/GPIO11") (class "Default")
      (node (ref "J1") (pin "14") (pinfunction "14_14") (pintype "passive"))
      (node (ref "U1") (pin "15") (pinfunction "GPIO11,_RTC_GPIO11,_TOUCH11,_ADC2_CH0,_FSPID,_FSPIIO5,_SUBSPID_15") (pintype "passive"))
    )
    (net (code "35") (name "/GPIO12") (class "Default")
      (node (ref "J1") (pin "15") (pinfunction "15_15") (pintype "passive"))
      (node (ref "U1") (pin "16") (pinfunction "GPIO12,_RTC_GPIO12,_TOUCH12,_ADC2_CH1,_FSPICLK,_FSPIIO6,_SUBSPICLK_16") (pintype "passive"))
    )
    (net (code "36") (name "/GPIO13") (class "Default")
      (node (ref "J1") (pin "16") (pinfunction "16_16") (pintype "passive"))
      (node (ref "U1") (pin "17") (pinfunction "GPIO13,_RTC_GPIO13,_TOUCH13,_ADC2_CH2,_FSPIQ,_FSPIIO7,_SUBSPIQ_17") (pintype "passive"))
    )
    (net (code "37") (name "/GPIO14") (class "Default")
      (node (ref "J1") (pin "17") (pinfunction "17_17") (pintype "passive"))
      (node (ref "U1") (pin "18") (pinfunction "GPIO14,_RTC_GPIO14,_TOUCH14,_ADC2_CH3,_FSPIWP,_FSPIDQS,_SUBSPIWP_18") (pintype "passive"))
    )
    (net (code "38") (name "/GPIO15") (class "Default")
      (node (ref "J1") (pin "18") (pinfunction "18_18") (pintype "passive"))
      (node (ref "U1") (pin "19") (pinfunction "GPIO15,_RTC_GPIO15,_U0RTS,_ADC2_CH4,_XTAL_32K_P_19") (pintype "passive"))
    )
    (net (code "39") (name "/GPIO16") (class "Default")
      (node (ref "J1") (pin "19") (pinfunction "19_19") (pintype "passive"))
      (node (ref "U1") (pin "20") (pinfunction "GPIO16,_RTC_GPIO16,_U0CTS,_ADC2_CH5,_XTAL_32K_N_20") (pintype "passive"))
    )
    (net (code "40") (name "/GPIO17") (class "Default")
      (node (ref "J1") (pin "20") (pinfunction "20_20") (pintype "passive"))
      (node (ref "U1") (pin "21") (pinfunction "GPIO17,_RTC_GPIO17,_U1TXD,_ADC2_CH6_21") (pintype "passive"))
    )
    (net (code "41") (name "/GPIO18") (class "Default")
      (node (ref "J1") (pin "21") (pinfunction "21_21") (pintype "passive"))
      (node (ref "U1") (pin "22") (pinfunction "GPIO18,_RTC_GPIO18,_U1RXD,_ADC2_CH7,_CLK_OUT3_22") (pintype "passive"))
    )
    (net (code "42") (name "/GPIO21") (class "Default")
      (node (ref "J2") (pin "19") (pinfunction "19_19") (pintype "passive"))
      (node (ref "U1") (pin "25") (pinfunction "GPIO21,_RTC_GPIO21_25") (pintype "passive"))
    )
    (net (code "43") (name "/GPIO26") (class "Default")
      (node (ref "J2") (pin "18") (pinfunction "18_18") (pintype "passive"))
      (node (ref "U1") (pin "26") (pinfunction "GPIO26,_SPICS1_26") (pintype "passive"))
    )
    (net (code "44") (name "/GPIO33") (class "Default")
      (node (ref "J2") (pin "17") (pinfunction "17_17") (pintype "passive"))
      (node (ref "U1") (pin "28") (pinfunction "GPIO33,_SPIIO4,_FSPIHD,_SUBSPIHD_28") (pintype "passive"))
    )
    (net (code "45") (name "/GPIO34") (class "Default")
      (node (ref "J2") (pin "16") (pinfunction "16_16") (pintype "passive"))
      (node (ref "U1") (pin "29") (pinfunction "GPIO34,_SPIIO5,_FSPICS0,_SUBSPICS0_29") (pintype "passive"))
    )
    (net (code "46") (name "/GPIO35") (class "Default")
      (node (ref "J2") (pin "15") (pinfunction "15_15") (pintype "passive"))
      (node (ref "U1") (pin "31") (pinfunction "GPIO35,_SPIIO6,_FSPID,_SUBSPID_31") (pintype "passive"))
    )
    (net (code "47") (name "/GPIO36") (class "Default")
      (node (ref "J2") (pin "14") (pinfunction "14_14") (pintype "passive"))
      (node (ref "U1") (pin "32") (pinfunction "GPIO36,_SPIIO7,_FSPICLK,_SUBSPICLK_32") (pintype "passive"))
    )
    (net (code "48") (name "/GPIO37") (class "Default")
      (node (ref "J2") (pin "13") (pinfunction "13_13") (pintype "passive"))
      (node (ref "U1") (pin "33") (pinfunction "GPIO37,_SPIDQS,_FSPIQ,_SUBSPIQ_33") (pintype "passive"))
    )
    (net (code "49") (name "/GPIO38") (class "Default")
      (node (ref "J2") (pin "12") (pinfunction "12_12") (pintype "passive"))
      (node (ref "U1") (pin "34") (pinfunction "GPIO38,_FSPIWP,_SUBSPIWP_34") (pintype "passive"))
    )
    (net (code "50") (name "/GPIO39") (class "Default")
      (node (ref "J2") (pin "11") (pinfunction "11_11") (pintype "passive"))
      (node (ref "U1") (pin "35") (pinfunction "GPIO39,_MTCK,_CLK_OUT3,_SUBSPICS1_35") (pintype "passive"))
    )
    (net (code "51") (name "/GPIO40") (class "Default")
      (node (ref "J2") (pin "10") (pinfunction "10_10") (pintype "passive"))
      (node (ref "U1") (pin "36") (pinfunction "GPIO40,_MTDO,_CLK_OUT2_36") (pintype "passive"))
    )
    (net (code "52") (name "/GPIO41") (class "Default")
      (node (ref "J2") (pin "9") (pinfunction "9_9") (pintype "passive"))
      (node (ref "U1") (pin "37") (pinfunction "GPIO41,_MTDI,_CLK_OUT1_37") (pintype "passive"))
    )
    (net (code "53") (name "/GPIO42") (class "Default")
      (node (ref "J2") (pin "8") (pinfunction "8_8") (pintype "passive"))
      (node (ref "U1") (pin "38") (pinfunction "GPIO42,_MTMS_38") (pintype "passive"))
    )
    (net (code "54") (name "/GPIO45") (class "Default")
      (node (ref "J2") (pin "5") (pinfunction "5_5") (pintype "passive"))
      (node (ref "U1") (pin "41") (pinfunction "GPIO45_41") (pintype "passive"))
    )
    (net (code "55") (name "/GPIO46") (class "Default")
      (node (ref "J2") (pin "4") (pinfunction "4_4") (pintype "passive"))
      (node (ref "U1") (pin "44") (pinfunction "GPIO46_44") (pintype "passive"))
    )
    (net (code "56") (name "/GPIO47") (class "Default")
      (node (ref "J2") (pin "23") (pinfunction "23_23") (pintype "passive"))
      (node (ref "U1") (pin "27") (pinfunction "GPIO47,_SPICLK_P_DIFF,_SUBSPICLK_P_DIFF_27") (pintype "passive"))
    )
    (net (code "57") (name "/GPIO48") (class "Default")
      (node (ref "J2") (pin "22") (pinfunction "22_22") (pintype "passive"))
      (node (ref "U1") (pin "30") (pinfunction "GPIO48,_SPICLK_N_DIFF,_SUBSPICLK_N_DIFF_30") (pintype "passive"))
    )
    (net (code "58") (name "/RTS_FTDI") (class "Default")
      (node (ref "Q1") (pin "2") (pinfunction "E_2") (pintype "passive"))
      (node (ref "R18") (pin "1") (pinfunction "1_1") (pintype "passive"))
      (node (ref "U2") (pin "19") (pinfunction "~{RTS}_19") (pintype "passive"))
    )
    (net (code "59") (name "/RXD_FTDI") (class "Default")
      (node (ref "R19") (pin "2") (pinfunction "2_2") (pintype "passive"))
      (node (ref "U2") (pin "1") (pinfunction "RXD_1") (pintype "passive"))
    )
    (net (code "60") (name "/TXD_FTDI") (class "Default")
      (node (ref "R20") (pin "2") (pinfunction "2_2") (pintype "passive"))
      (node (ref "U2") (pin "17") (pinfunction "TXD_17") (pintype "passive"))
    )
    (net (code "61") (name "/U0RXD") (class "Default")
      (node (ref "J2") (pin "6") (pinfunction "6_6") (pintype "passive"))
      (node (ref "R20") (pin "1") (pinfunction "1_1") (pintype "passive"))
      (node (ref "U1") (pin "40") (pinfunction "GPIO44,_U0RXD,_CLK_OUT2_40") (pintype "passive"))
    )
    (net (code "62") (name "/U0TXD") (class "Default")
      (node (ref "J2") (pin "7") (pinfunction "7_7") (pintype "passive"))
      (node (ref "R19") (pin "1") (pinfunction "1_1") (pintype "passive"))
      (node (ref "U1") (pin "39") (pinfunction "GPIO43,_U0TXD,_CLK_OUT1_39") (pintype "passive"))
    )
    (net (code "63") (name "/VBUS_SENSE") (class "Default")
      (node (ref "R10") (pin "1") (pinfunction "1_1") (pintype "passive"))
      (node (ref "R13") (pin "2") (pinfunction "2_2") (pintype "passive"))
      (node (ref "U2") (pin "16") (pinfunction "CBUS3_16") (pintype "passive"))
    )
    (net (code "64") (name "GND") (class "Default")
      (node (ref "C1") (pin "1") (pinfunction "1_1") (pintype "passive"))
      (node (ref "C10") (pin "1") (pinfunction "1_1") (pintype "passive"))
      (node (ref "C11") (pin "1") (pinfunction "1_1") (pintype "passive"))
      (node (ref "C12") (pin "1") (pinfunction "1_1") (pintype "passive"))
      (node (ref "C13") (pin "1") (pinfunction "1_1") (pintype "passive"))
      (node (ref "C14") (pin "1") (pinfunction "1_1") (pintype "passive"))
      (node (ref "C15") (pin "1") (pinfunction "1_1") (pintype "passive"))
      (node (ref "C16") (pin "1") (pinfunction "1_1") (pintype "passive"))
      (node (ref "C17") (pin "1") (pinfunction "1_1") (pintype "passive"))
      (node (ref "C2") (pin "1") (pinfunction "1_1") (pintype "passive"))
      (node (ref "C3") (pin "2") (pinfunction "2_2") (pintype "passive"))
      (node (ref "C4") (pin "1") (pinfunction "1_1") (pintype "passive"))
      (node (ref "C5") (pin "1") (pinfunction "1_1") (pintype "passive"))
      (node (ref "C6") (pin "2") (pinfunction "2_2") (pintype "passive"))
      (node (ref "C7") (pin "2") (pinfunction "2_2") (pintype "passive"))
      (node (ref "C8") (pin "2") (pinfunction "2_2") (pintype "passive"))
      (node (ref "C9") (pin "1") (pinfunction "1_1") (pintype "passive"))
      (node (ref "D1") (pin "1") (pinfunction "1_1") (pintype "passive"))
      (node (ref "D3") (pin "1") (pinfunction "1_1") (pintype "passive"))
      (node (ref "D4") (pin "1") (pinfunction "1_1") (pintype "passive"))
      (node (ref "D5") (pin "1") (pinfunction "1_1") (pintype "passive"))
      (node (ref "D6") (pin "1") (pinfunction "1_1") (pintype "passive"))
      (node (ref "D7") (pin "1") (pinfunction "1_1") (pintype "passive"))
      (node (ref "D8") (pin "1") (pinfunction "1_1") (pintype "passive"))
      (node (ref "J1") (pin "1") (pinfunction "1_1") (pintype "passive"))
      (node (ref "J1") (pin "23") (pinfunction "23_23") (pintype "passive"))
      (node (ref "J2") (pin "2") (pinfunction "2_2") (pintype "passive"))
      (node (ref "J2") (pin "24") (pinfunction "24_24") (pintype "passive"))
      (node (ref "J3") (pin "A1B12") (pinfunction "GND_A1B12_A1B12") (pintype "passive"))
      (node (ref "J3") (pin "B1A12") (pinfunction "GND_B1A12_B1A12") (pintype "passive"))
      (node (ref "J3") (pin "S1") (pinfunction "SHEILD_1_S1") (pintype "passive"))
      (node (ref "J3") (pin "S2") (pinfunction "SHEILD_2_S2") (pintype "passive"))
      (node (ref "J3") (pin "S3") (pinfunction "SHEILD_3_S3") (pintype "passive"))
      (node (ref "J3") (pin "S4") (pinfunction "SHEILD_4_S4") (pintype "passive"))
      (node (ref "J4") (pin "A1B12") (pinfunction "GND_A1B12_A1B12") (pintype "passive"))
      (node (ref "J4") (pin "B1A12") (pinfunction "GND_B1A12_B1A12") (pintype "passive"))
      (node (ref "J4") (pin "S1") (pinfunction "SHEILD_1_S1") (pintype "passive"))
      (node (ref "J4") (pin "S2") (pinfunction "SHEILD_2_S2") (pintype "passive"))
      (node (ref "J4") (pin "S3") (pinfunction "SHEILD_3_S3") (pintype "passive"))
      (node (ref "J4") (pin "S4") (pinfunction "SHEILD_4_S4") (pintype "passive"))
      (node (ref "R11") (pin "1") (pinfunction "1_1") (pintype "passive"))
      (node (ref "R12") (pin "1") (pinfunction "1_1") (pintype "passive"))
      (node (ref "R13") (pin "1") (pinfunction "1_1") (pintype "passive"))
      (node (ref "R14") (pin "1") (pinfunction "1_1") (pintype "passive"))
      (node (ref "R15") (pin "1") (pinfunction "1_1") (pintype "passive"))
      (node (ref "R9") (pin "2") (pinfunction "2_2") (pintype "passive"))
      (node (ref "SW1") (pin "3") (pinfunction "3_3") (pintype "passive"))
      (node (ref "SW1") (pin "4") (pinfunction "4_4") (pintype "passive"))
      (node (ref "SW2") (pin "3") (pinfunction "3_3") (pintype "passive"))
      (node (ref "SW2") (pin "4") (pinfunction "4_4") (pintype "passive"))
      (node (ref "U1") (pin "1") (pinfunction "GND_1_1") (pintype "passive"))
      (node (ref "U1") (pin "2") (pinfunction "GND_2_2") (pintype "passive"))
      (node (ref "U1") (pin "42") (pinfunction "GND_42_42") (pintype "passive"))
      (node (ref "U1") (pin "43") (pinfunction "GND,GND_43") (pintype "passive"))
      (node (ref "U1") (pin "46") (pinfunction "GND_46_46") (pintype "passive"))
      (node (ref "U1") (pin "47") (pinfunction "GND_47_47") (pintype "passive"))
      (node (ref "U1") (pin "48") (pinfunction "GND_48_48") (pintype "passive"))
      (node (ref "U1") (pin "49") (pinfunction "GND_49_49") (pintype "passive"))
      (node (ref "U1") (pin "50") (pinfunction "GND_50_50") (pintype "passive"))
      (node (ref "U1") (pin "51") (pinfunction "GND_51_51") (pintype "passive"))
      (node (ref "U1") (pin "52") (pinfunction "GND_52_52") (pintype "passive"))
      (node (ref "U1") (pin "53") (pinfunction "GND_53_53") (pintype "passive"))
      (node (ref "U1") (pin "54") (pinfunction "GND_54_54") (pintype "passive"))
      (node (ref "U1") (pin "55") (pinfunction "GND_55_55") (pintype "passive"))
      (node (ref "U1") (pin "56") (pinfunction "GND_56_56") (pintype "passive"))
      (node (ref "U1") (pin "57") (pinfunction "GND_57_57") (pintype "passive"))
      (node (ref "U1") (pin "58") (pinfunction "GND_58_58") (pintype "passive"))
      (node (ref "U1") (pin "59") (pinfunction "GND_59_59") (pintype "passive"))
      (node (ref "U1") (pin "60") (pinfunction "GND_60_60") (pintype "passive"))
      (node (ref "U1") (pin "61") (pinfunction "GND_61_61") (pintype "passive"))
      (node (ref "U1") (pin "62") (pinfunction "GND_62_62") (pintype "passive"))
      (node (ref "U1") (pin "63") (pinfunction "GND_63_63") (pintype "passive"))
      (node (ref "U1") (pin "64") (pinfunction "GND_64_64") (pintype "passive"))
      (node (ref "U1") (pin "65") (pinfunction "GND_65_65") (pintype "passive"))
      (node (ref "U1") (pin "66") (pinfunction "GND_66_66") (pintype "passive"))
      (node (ref "U1") (pin "67") (pinfunction "GND_67_67") (pintype "passive"))
      (node (ref "U1") (pin "68") (pinfunction "GND_68_68") (pintype "passive"))
      (node (ref "U1") (pin "69") (pinfunction "GND_69_69") (pintype "passive"))
      (node (ref "U1") (pin "70") (pinfunction "GND_70_70") (pintype "passive"))
      (node (ref "U1") (pin "71") (pinfunction "GND_71_71") (pintype "passive"))
      (node (ref "U1") (pin "72") (pinfunction "GND_72_72") (pintype "passive"))
      (node (ref "U1") (pin "73") (pinfunction "GND_73_73") (pintype "passive"))
      (node (ref "U2") (pin "13") (pinfunction "GND_13") (pintype "passive"))
      (node (ref "U2") (pin "21") (pinfunction "GND_21") (pintype "passive"))
      (node (ref "U2") (pin "3") (pinfunction "GND_3") (pintype "passive"))
      (node (ref "U3") (pin "2") (pinfunction "GND_2") (pintype "power_in"))
      (node (ref "U3") (pin "4") (pinfunction "GND_4") (pintype "power_in"))
    )
    (net (code "65") (name "Net-(D1-Pad2)") (class "Default")
      (node (ref "D1") (pin "2") (pinfunction "2_2") (pintype "passive"))
      (node (ref "R3") (pin "1") (pinfunction "1_1") (pintype "passive"))
    )
    (net (code "66") (name "Net-(D2-Pad2)") (class "Default")
      (node (ref "D2") (pin "2") (pinfunction "2_2") (pintype "passive"))
      (node (ref "R4") (pin "1") (pinfunction "1_1") (pintype "passive"))
    )
    (net (code "67") (name "Net-(J3-CC1)") (class "Default")
      (node (ref "J3") (pin "A5") (pinfunction "CC1_A5") (pintype "passive"))
      (node (ref "R11") (pin "2") (pinfunction "2_2") (pintype "passive"))
    )
    (net (code "68") (name "Net-(J3-CC2)") (class "Default")
      (node (ref "J3") (pin "B5") (pinfunction "CC2_B5") (pintype "passive"))
      (node (ref "R12") (pin "2") (pinfunction "2_2") (pintype "passive"))
    )
    (net (code "69") (name "Net-(J4-CC1)") (class "Default")
      (node (ref "J4") (pin "A5") (pinfunction "CC1_A5") (pintype "passive"))
      (node (ref "R14") (pin "2") (pinfunction "2_2") (pintype "passive"))
    )
    (net (code "70") (name "Net-(J4-CC2)") (class "Default")
      (node (ref "J4") (pin "B5") (pinfunction "CC2_B5") (pintype "passive"))
      (node (ref "R15") (pin "2") (pinfunction "2_2") (pintype "passive"))
    )
    (net (code "71") (name "Net-(Q1-B)") (class "Default")
      (node (ref "Q1") (pin "1") (pinfunction "B_1") (pintype "passive"))
      (node (ref "R16") (pin "2") (pinfunction "2_2") (pintype "passive"))
    )
    (net (code "72") (name "Net-(Q2-B)") (class "Default")
      (node (ref "Q2") (pin "1") (pinfunction "B_1") (pintype "passive"))
      (node (ref "R18") (pin "2") (pinfunction "2_2") (pintype "passive"))
    )
    (net (code "73") (name "Net-(U2-CBUS0)") (class "Default")
      (node (ref "R9") (pin "1") (pinfunction "1_1") (pintype "passive"))
      (node (ref "U2") (pin "15") (pinfunction "CBUS0_15") (pintype "passive"))
    )
    (net (code "74") (name "unconnected-(J1-Pad24)") (class "Default")
      (node (ref "J1") (pin "24") (pinfunction "24_24") (pintype "passive+no_connect"))
    )
    (net (code "75") (name "unconnected-(J3-SBU2-PadB8)") (class "Default")
      (node (ref "J3") (pin "B8") (pinfunction "SBU2_B8") (pintype "passive+no_connect"))
    )
    (net (code "76") (name "unconnected-(J3-SUB1-PadA8)") (class "Default")
      (node (ref "J3") (pin "A8") (pinfunction "SUB1_A8") (pintype "passive+no_connect"))
    )
    (net (code "77") (name "unconnected-(J4-SBU2-PadB8)") (class "Default")
      (node (ref "J4") (pin "B8") (pinfunction "SBU2_B8") (pintype "passive+no_connect"))
    )
    (net (code "78") (name "unconnected-(J4-SUB1-PadA8)") (class "Default")
      (node (ref "J4") (pin "A8") (pinfunction "SUB1_A8") (pintype "passive+no_connect"))
    )
    (net (code "79") (name "unconnected-(U2-CBUS1-Pad14)") (class "Default")
      (node (ref "U2") (pin "14") (pinfunction "CBUS1_14") (pintype "passive+no_connect"))
    )
    (net (code "80") (name "unconnected-(U2-CBUS2-Pad7)") (class "Default")
      (node (ref "U2") (pin "7") (pinfunction "CBUS2_7") (pintype "passive+no_connect"))
    )
    (net (code "81") (name "unconnected-(U2-~{CTS}-Pad6)") (class "Default")
      (node (ref "U2") (pin "6") (pinfunction "~{CTS}_6") (pintype "passive+no_connect"))
    )
    (net (code "82") (name "unconnected-(U2-~{DCD}-Pad5)") (class "Default")
      (node (ref "U2") (pin "5") (pinfunction "~{DCD}_5") (pintype "passive+no_connect"))
    )
    (net (code "83") (name "unconnected-(U2-~{DSR}-Pad4)") (class "Default")
      (node (ref "U2") (pin "4") (pinfunction "~{DSR}_4") (pintype "passive+no_connect"))
    )
    (net (code "84") (name "unconnected-(U2-~{RI}-Pad2)") (class "Default")
      (node (ref "U2") (pin "2") (pinfunction "~{RI}_2") (pintype "passive+no_connect"))
    )
  )
)
